# ESP32_WI-FI_Module.net
KiCad netlist of a schematic drawn in Altium Designer
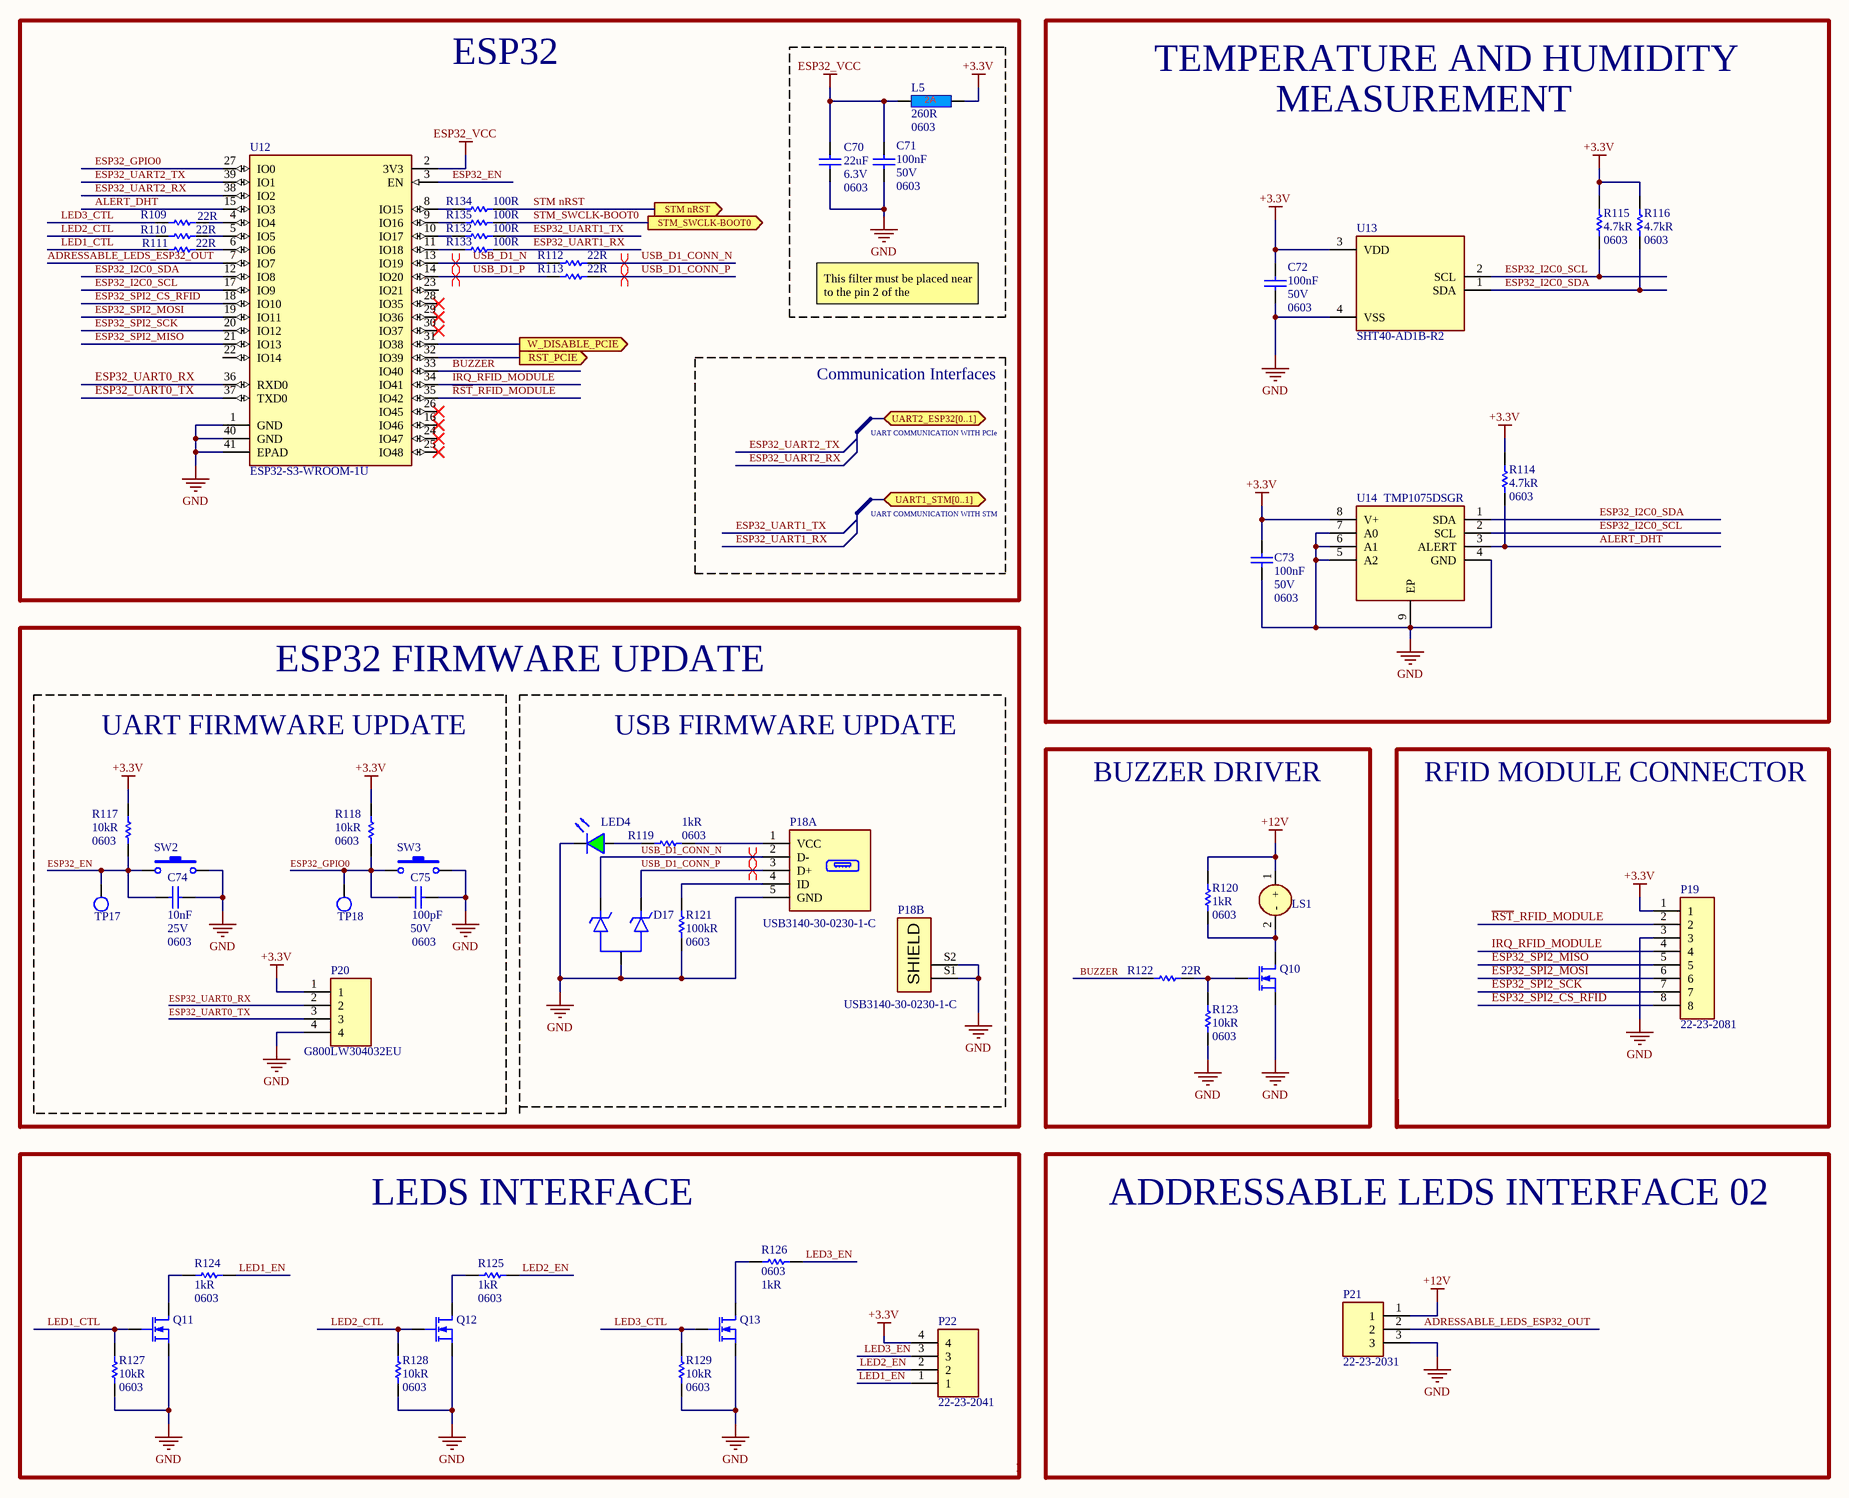
[diagram p0: ESP32 WI-FI Module.SchDoc]

(export (version "E")
  (design (tool "Eeschema 10.0.6"))
  (components
    (comp (ref "C70")
      (value "C_0603_22uF_6.3V_20%")
      (footprint "C0603")
      (description "CAP CER 22UF 6.3V X5R 0603")
      (fields
        (field (name "MANUFACTURER") "Murata")
        (field (name "MANUFACTURER PART NUMBER") "GRM188R60J226MEA0J")
        (field (name "CASE/PACKAGE") "0603")
        (field (name "VOLTAGE RATING (DC)") "6.3V")
        (field (name "CAPACITANCE") "22uF")
      )
      (libsource (lib "Power2Go - REV05") (part "C_0603_22uF_6.3V_20%"))
    )
    (comp (ref "C71")
      (value "100nF")
      (footprint "C0603")
      (description "Cap Ceramic 50V 20% +Tol 20% -Tol X7R 15% TC 0.1uF SMD 0603")
      (fields
        (field (name "MANUFACTURER") "Yageo")
        (field (name "MANUFACTURER PART NUMBER") "CC0603MRX7R9BB104")
        (field (name "CASE/PACKAGE") "0603")
        (field (name "VOLTAGE RATING") "50V")
      )
      (libsource (lib "Power2Go - REV05") (part "C_0603_0.1uF_50V_20%"))
    )
    (comp (ref "C72")
      (value "100nF")
      (footprint "C0603")
      (description "Cap Ceramic 50V 20% +Tol 20% -Tol X7R 15% TC 0.1uF SMD 0603")
      (fields
        (field (name "MANUFACTURER") "Yageo")
        (field (name "MANUFACTURER PART NUMBER") "CC0603MRX7R9BB104")
        (field (name "CASE/PACKAGE") "0603")
        (field (name "VOLTAGE RATING") "50V")
      )
      (libsource (lib "Power2Go - REV05") (part "C_0603_0.1uF_50V_20%"))
    )
    (comp (ref "C73")
      (value "100nF")
      (footprint "C0603")
      (description "Cap Ceramic 50V 20% +Tol 20% -Tol X7R 15% TC 0.1uF SMD 0603")
      (fields
        (field (name "MANUFACTURER") "Yageo")
        (field (name "MANUFACTURER PART NUMBER") "CC0603MRX7R9BB104")
        (field (name "CASE/PACKAGE") "0603")
        (field (name "VOLTAGE RATING") "50V")
      )
      (libsource (lib "Power2Go - REV05") (part "C_0603_0.1uF_50V_20%"))
    )
    (comp (ref "C74")
      (value "C_0603_0.01uF_25V_10%")
      (footprint "C0603")
      (description "Surface Mount Ceramic Multilayer Capacitor 0.01uF 10% X7R 25V 0603 Paper T/R")
      (fields
        (field (name "MANUFACTURER") "Yageo")
        (field (name "MANUFACTURER PART NUMBER") "CC0603KRX7R8BB103")
        (field (name "VOLTAGE RATING") "25V")
        (field (name "CAPACITANCE") "10nF")
        (field (name "CASE CODE (IMPERIAL)") "0603")
      )
      (libsource (lib "Power2Go - REV05") (part "C_0603_0.01uF_25V_10%"))
    )
    (comp (ref "C75")
      (value "100pF")
      (footprint "C0603")
      (description "Ceramic capacitor SMD-0603 100pF /50V NP0# J +-5%, Samsung, RoHS")
      (fields
        (field (name "MANUFACTURER") "Samsung")
        (field (name "MANUFACTURER PART NUMBER") "CL10C101JB8NNNC")
        (field (name "VOLTAGE") "50V")
        (field (name "CASE/PACKAGE") "0603")
      )
      (libsource (lib "Power2Go - REV05") (part "C_0603_100pF_50V_5%"))
    )
    (comp (ref "D17")
      (value "RCLAMP0502BATCT")
      (footprint "SC-75-3")
      (description "ESD Suppressor Diode TVS Uni-Dir/Bi-Dir 5V 3-Pin SOT-523 T/R / TVS DIODE 5VWM 25VC SC75")
      (fields (field (name "MANUFACTURER") "Semtech"))
      (libsource (lib "Power2Go - REV05") (part "D_TVS_RCLAMP0502BATCT"))
    )
    (comp (ref "L5")
      (value "BLM18EG221SN1D")
      (footprint "L0603")
      (description "Ferrite Chip, 1 Function(s), 1A, 2 Pin(s)")
      (fields
        (field (name "MANUFACTURER") "Murata")
        (field (name "CASE CODE") "0603")
        (field (name "OUTPUT IMPEDANCE") "260R")
      )
      (libsource (lib "Power2Go - REV05") (part "L_0603_25%_2A"))
    )
    (comp (ref "LED4")
      (value "LED 0603 SMD GREEN")
      (footprint "LED0603-GREEN")
      (description "Smd, Alingap, 0603, Thin, Grn, 571Nm, 35Mcd, Clr, T/R Rohs Compliant: Yes")
      (fields
        (field (name "MANUFACTURER") "Vishay Lite-On")
        (field (name "MANUFACTURER PART NUMBER") "LTST-C191KGKT")
      )
      (libsource (lib "Power2Go - REV05") (part "LED_0603_Green"))
    )
    (comp (ref "LS1")
      (value "PS1240P02BT")
      (footprint "BZ_12mm")
      (description "Piezo Buzzers & Audio Indicators Round 12.2mmx6.5mm 4kHz Vin=3V")
      (fields (field (name "MANUFACTURER") "TDK"))
      (libsource (lib "Power2Go - REV05") (part "LS_BUZZER_12mm"))
    )
    (comp (ref "P18")
      (value "USB3140-30-0230-1-C")
      (footprint "CONN-MICROUSB-VERT")
      (description "Conn Micro USB Type B RCP 2Power/3Signal POS Solder ST SMD 5 Terminal 2 Port T/R")
      (fields
        (field (name "MANUFACTURER") "Global Connector Technology")
        (field (name "MANUFACTURER PART NUMBER") "USB3140-30-0230-1-C")
      )
      (libsource (lib "Power2Go - REV05") (part "P_MicroUSB_TypeB"))
    )
    (comp (ref "P19")
      (value "22-23-2081")
      (footprint "HEADER_KK_2.54MM_8POS")
      (description "KK 254 Solid Header, Vertical, with Friction Lock, 8 Circuits, Tin (Sn) Plating")
      (fields (field (name "MANUFACTURER") "Molex") (field (name "MANUFACTURER PART NUMBER") "22-23-2081"))
      (libsource (lib "Power2Go - REV05") (part "P_Molex_HEADER_KK_8POS_2.54MM_PTH"))
    )
    (comp (ref "P20")
      (value "G800LW304032EU")
      (footprint "HEADER_2.54MM_4POS")
      (description "Board to Board Connector Straight Header Single Row 4 Position 2.54mm Pitch Through Hole Bag")
      (fields
        (field (name "MANUFACTURER") "Amphenol")
        (field (name "MANUFACTURER PART NUMBER") "G800LW304032EU")
      )
      (libsource (lib "Power2Go - REV05") (part "P_Header_2.54mm_4POS"))
    )
    (comp (ref "P21")
      (value "22-23-2031")
      (footprint "HEADER_2.54MM_3POS")
      (description "KK 254 Solid Header, Vertical, with Friction Lock, 3 Circuits, Tin (Sn) Plating, Bag")
      (fields (field (name "MANUFACTURER") "Molex") (field (name "MANUFACTURER PART NUMBER") "22-23-2031"))
      (libsource (lib "Power2Go - REV05") (part "P_Molex_HEADER_3POS_2.54MM_PTH"))
    )
    (comp (ref "P22")
      (value "22-23-2041")
      (footprint "HEADER_KK_2.54MM_4POS")
      (description "KK 254 Solid Header, Vertical, with Friction Lock, 4 Circuits, Tin (Sn) Plating")
      (fields (field (name "MANUFACTURER") "Molex"))
      (libsource (lib "Power2Go - REV05") (part "P_Molex_HEADER_KK_4POS_2.54MM_PTH"))
    )
    (comp (ref "Q10")
      (value "RSF015N06FRATL")
      (footprint "TUMT-3")
      (description "Transistor Mosfet N-ch 60V 1.5A 3-PIN Tumt T/r")
      (fields (field (name "MANUFACTURER") "Rohm"))
      (libsource (lib "Power2Go - REV05") (part "Q_RSF015N06FRATL_TUMT-3"))
    )
    (comp (ref "Q11")
      (value "RSF015N06FRATL")
      (footprint "TUMT-3")
      (description "Transistor Mosfet N-ch 60V 1.5A 3-PIN Tumt T/r")
      (fields (field (name "MANUFACTURER") "Rohm"))
      (libsource (lib "Power2Go - REV05") (part "Q_RSF015N06FRATL_TUMT-3"))
    )
    (comp (ref "Q12")
      (value "RSF015N06FRATL")
      (footprint "TUMT-3")
      (description "Transistor Mosfet N-ch 60V 1.5A 3-PIN Tumt T/r")
      (fields (field (name "MANUFACTURER") "Rohm"))
      (libsource (lib "Power2Go - REV05") (part "Q_RSF015N06FRATL_TUMT-3"))
    )
    (comp (ref "Q13")
      (value "RSF015N06FRATL")
      (footprint "TUMT-3")
      (description "Transistor Mosfet N-ch 60V 1.5A 3-PIN Tumt T/r")
      (fields (field (name "MANUFACTURER") "Rohm"))
      (libsource (lib "Power2Go - REV05") (part "Q_RSF015N06FRATL_TUMT-3"))
    )
    (comp (ref "R109")
      (value "CRCW060322R0FKEAC")
      (footprint "R0603")
      (description "Thick Film Resistors - SMD 1/10Watt 22ohms 1% Commercial Use")
      (fields
        (field (name "MANUFACTURER") "Vishay")
        (field (name "TOLERANCE") "1%")
        (field (name "RESISTANCE") "22R")
      )
      (libsource (lib "Power2Go - REV05") (part "R_0603_22R_1%_1/10W"))
    )
    (comp (ref "R110")
      (value "CRCW060322R0FKEAC")
      (footprint "R0603")
      (description "Thick Film Resistors - SMD 1/10Watt 22ohms 1% Commercial Use")
      (fields
        (field (name "MANUFACTURER") "Vishay")
        (field (name "TOLERANCE") "1%")
        (field (name "RESISTANCE") "22R")
      )
      (libsource (lib "Power2Go - REV05") (part "R_0603_22R_1%_1/10W"))
    )
    (comp (ref "R111")
      (value "CRCW060322R0FKEAC")
      (footprint "R0603")
      (description "Thick Film Resistors - SMD 1/10Watt 22ohms 1% Commercial Use")
      (fields
        (field (name "MANUFACTURER") "Vishay")
        (field (name "TOLERANCE") "1%")
        (field (name "RESISTANCE") "22R")
      )
      (libsource (lib "Power2Go - REV05") (part "R_0603_22R_1%_1/10W"))
    )
    (comp (ref "R112")
      (value "CRCW060322R0FKEAC")
      (footprint "R0603")
      (description "Thick Film Resistors - SMD 1/10Watt 22ohms 1% Commercial Use")
      (fields
        (field (name "MANUFACTURER") "Vishay")
        (field (name "TOLERANCE") "1%")
        (field (name "RESISTANCE") "22R")
      )
      (libsource (lib "Power2Go - REV05") (part "R_0603_22R_1%_1/10W"))
    )
    (comp (ref "R113")
      (value "CRCW060322R0FKEAC")
      (footprint "R0603")
      (description "Thick Film Resistors - SMD 1/10Watt 22ohms 1% Commercial Use")
      (fields
        (field (name "MANUFACTURER") "Vishay")
        (field (name "TOLERANCE") "1%")
        (field (name "RESISTANCE") "22R")
      )
      (libsource (lib "Power2Go - REV05") (part "R_0603_22R_1%_1/10W"))
    )
    (comp (ref "R114")
      (value "R_0603_4.7k_1%_1/10W")
      (footprint "R0603")
      (description "Res Thick Film 0603 4.7K Ohm 1% 0.1W(1/10W) ±100ppm/C Pad SMD T/R")
      (fields
        (field (name "TOLERANCE") "1%")
        (field (name "MANUFACTURER") "Mitsubishi Kamaya")
        (field (name "CASE CODE (IMPERIAL)") "0603")
        (field (name "RESISTANCE") "4.7kR")
      )
      (libsource (lib "Power2Go - REV05") (part "R_0603_4.7k_1%_1/10W"))
    )
    (comp (ref "R115")
      (value "R_0603_4.7k_1%_1/10W")
      (footprint "R0603")
      (description "Res Thick Film 0603 4.7K Ohm 1% 0.1W(1/10W) ±100ppm/C Pad SMD T/R")
      (fields
        (field (name "TOLERANCE") "1%")
        (field (name "MANUFACTURER") "Mitsubishi Kamaya")
        (field (name "CASE CODE (IMPERIAL)") "0603")
        (field (name "RESISTANCE") "4.7kR")
      )
      (libsource (lib "Power2Go - REV05") (part "R_0603_4.7k_1%_1/10W"))
    )
    (comp (ref "R116")
      (value "R_0603_4.7k_1%_1/10W")
      (footprint "R0603")
      (description "Res Thick Film 0603 4.7K Ohm 1% 0.1W(1/10W) ±100ppm/C Pad SMD T/R")
      (fields
        (field (name "TOLERANCE") "1%")
        (field (name "MANUFACTURER") "Mitsubishi Kamaya")
        (field (name "CASE CODE (IMPERIAL)") "0603")
        (field (name "RESISTANCE") "4.7kR")
      )
      (libsource (lib "Power2Go - REV05") (part "R_0603_4.7k_1%_1/10W"))
    )
    (comp (ref "R117")
      (value "10kR")
      (footprint "R0603")
      (fields
        (field (name "MANUFACTURER") "Vishay")
        (field (name "MANUFACTURER PART NUMBER") "CRCW060310K0JNEBC")
        (field (name "TOLERANCE") "5%")
        (field (name "CASE/PACKAGE") "0603")
      )
      (libsource (lib "Power2Go - REV05") (part "R_0603_10kR_5%_1/10W"))
    )
    (comp (ref "R118")
      (value "10kR")
      (footprint "R0603")
      (fields
        (field (name "MANUFACTURER") "Vishay")
        (field (name "MANUFACTURER PART NUMBER") "CRCW060310K0JNEBC")
        (field (name "TOLERANCE") "5%")
        (field (name "CASE/PACKAGE") "0603")
      )
      (libsource (lib "Power2Go - REV05") (part "R_0603_10kR_5%_1/10W"))
    )
    (comp (ref "R119")
      (value "R_0603_1kR_1%_1/10W")
      (footprint "R0603")
      (description "Res Thick Film 0603 1K Ohm 1% 1/10W ±100ppm/°C Molded SMD Paper T/R")
      (fields
        (field (name "MANUFACTURER") "Vishay")
        (field (name "MANUFACTURER PART NUMBER") "CRCW06031K00FKEAC")
        (field (name "SIZE CODE") "0603")
        (field (name "RESISTANCE") "1kR")
      )
      (libsource (lib "Power2Go - REV05") (part "R_0603_1kR_1%_1/10W"))
    )
    (comp (ref "R120")
      (value "R_0603_1kR_1%_1/10W")
      (footprint "R0603")
      (description "Res Thick Film 0603 1K Ohm 1% 1/10W ±100ppm/°C Molded SMD Paper T/R")
      (fields
        (field (name "MANUFACTURER") "Vishay")
        (field (name "MANUFACTURER PART NUMBER") "CRCW06031K00FKEAC")
        (field (name "SIZE CODE") "0603")
        (field (name "RESISTANCE") "1kR")
      )
      (libsource (lib "Power2Go - REV05") (part "R_0603_1kR_1%_1/10W"))
    )
    (comp (ref "R121")
      (value "RC0603FR-07100KL")
      (footprint "R0603")
      (description "Thick Film Resistors - SMD 100K OHM 1%")
      (fields
        (field (name "MANUFACTURER") "Yageo")
        (field (name "TOLERANCE") "1%")
        (field (name "CASE/PACKAGE") "0603")
        (field (name "RESISTANCE") "100kR")
      )
      (libsource (lib "Power2Go - REV05") (part "R_0603_100k_1%_1/10W"))
    )
    (comp (ref "R122")
      (value "CRCW060322R0FKEAC")
      (footprint "R0603")
      (description "Thick Film Resistors - SMD 1/10Watt 22ohms 1% Commercial Use")
      (fields
        (field (name "MANUFACTURER") "Vishay")
        (field (name "TOLERANCE") "1%")
        (field (name "RESISTANCE") "22R")
      )
      (libsource (lib "Power2Go - REV05") (part "R_0603_22R_1%_1/10W"))
    )
    (comp (ref "R123")
      (value "10kR")
      (footprint "R0603")
      (fields
        (field (name "MANUFACTURER") "Vishay")
        (field (name "MANUFACTURER PART NUMBER") "CRCW060310K0JNEBC")
        (field (name "TOLERANCE") "5%")
        (field (name "CASE/PACKAGE") "0603")
      )
      (libsource (lib "Power2Go - REV05") (part "R_0603_10kR_5%_1/10W"))
    )
    (comp (ref "R124")
      (value "R_0603_1kR_1%_1/10W")
      (footprint "R0603")
      (description "Res Thick Film 0603 1K Ohm 1% 1/10W ±100ppm/°C Molded SMD Paper T/R")
      (fields
        (field (name "MANUFACTURER") "Vishay")
        (field (name "MANUFACTURER PART NUMBER") "CRCW06031K00FKEAC")
        (field (name "SIZE CODE") "0603")
        (field (name "RESISTANCE") "1kR")
      )
      (libsource (lib "Power2Go - REV05") (part "R_0603_1kR_1%_1/10W"))
    )
    (comp (ref "R125")
      (value "R_0603_1kR_1%_1/10W")
      (footprint "R0603")
      (description "Res Thick Film 0603 1K Ohm 1% 1/10W ±100ppm/°C Molded SMD Paper T/R")
      (fields
        (field (name "MANUFACTURER") "Vishay")
        (field (name "MANUFACTURER PART NUMBER") "CRCW06031K00FKEAC")
        (field (name "SIZE CODE") "0603")
        (field (name "RESISTANCE") "1kR")
      )
      (libsource (lib "Power2Go - REV05") (part "R_0603_1kR_1%_1/10W"))
    )
    (comp (ref "R126")
      (value "R_0603_1kR_1%_1/10W")
      (footprint "R0603")
      (description "Res Thick Film 0603 1K Ohm 1% 1/10W ±100ppm/°C Molded SMD Paper T/R")
      (fields
        (field (name "MANUFACTURER") "Vishay")
        (field (name "MANUFACTURER PART NUMBER") "CRCW06031K00FKEAC")
        (field (name "SIZE CODE") "0603")
        (field (name "RESISTANCE") "1kR")
      )
      (libsource (lib "Power2Go - REV05") (part "R_0603_1kR_1%_1/10W"))
    )
    (comp (ref "R127")
      (value "10kR")
      (footprint "R0603")
      (fields
        (field (name "MANUFACTURER") "Vishay")
        (field (name "MANUFACTURER PART NUMBER") "CRCW060310K0JNEBC")
        (field (name "TOLERANCE") "5%")
        (field (name "CASE/PACKAGE") "0603")
      )
      (libsource (lib "Power2Go - REV05") (part "R_0603_10kR_5%_1/10W"))
    )
    (comp (ref "R128")
      (value "10kR")
      (footprint "R0603")
      (fields
        (field (name "MANUFACTURER") "Vishay")
        (field (name "MANUFACTURER PART NUMBER") "CRCW060310K0JNEBC")
        (field (name "TOLERANCE") "5%")
        (field (name "CASE/PACKAGE") "0603")
      )
      (libsource (lib "Power2Go - REV05") (part "R_0603_10kR_5%_1/10W"))
    )
    (comp (ref "R129")
      (value "10kR")
      (footprint "R0603")
      (fields
        (field (name "MANUFACTURER") "Vishay")
        (field (name "MANUFACTURER PART NUMBER") "CRCW060310K0JNEBC")
        (field (name "TOLERANCE") "5%")
        (field (name "CASE/PACKAGE") "0603")
      )
      (libsource (lib "Power2Go - REV05") (part "R_0603_10kR_5%_1/10W"))
    )
    (comp (ref "R132")
      (value "100R")
      (footprint "R0603")
      (description "Res Thin Film 0603 100 Ohm 1% 1/10W ±25ppm/°C Molded SMD Paper Tape on Plastic Reel")
      (fields
        (field (name "MANUFACTURER") "Bourns")
        (field (name "MANUFACTURER PART NUMBER") "CRT0603-FY-1000ELF")
      )
      (libsource (lib "Power2Go - REV05") (part "R_0603_100R_1%_1/10W_25PPM"))
    )
    (comp (ref "R133")
      (value "100R")
      (footprint "R0603")
      (description "Res Thin Film 0603 100 Ohm 1% 1/10W ±25ppm/°C Molded SMD Paper Tape on Plastic Reel")
      (fields
        (field (name "MANUFACTURER") "Bourns")
        (field (name "MANUFACTURER PART NUMBER") "CRT0603-FY-1000ELF")
      )
      (libsource (lib "Power2Go - REV05") (part "R_0603_100R_1%_1/10W_25PPM"))
    )
    (comp (ref "R134")
      (value "100R")
      (footprint "R0603")
      (description "Res Thin Film 0603 100 Ohm 1% 1/10W ±25ppm/°C Molded SMD Paper Tape on Plastic Reel")
      (fields
        (field (name "MANUFACTURER") "Bourns")
        (field (name "MANUFACTURER PART NUMBER") "CRT0603-FY-1000ELF")
      )
      (libsource (lib "Power2Go - REV05") (part "R_0603_100R_1%_1/10W_25PPM"))
    )
    (comp (ref "R135")
      (value "100R")
      (footprint "R0603")
      (description "Res Thin Film 0603 100 Ohm 1% 1/10W ±25ppm/°C Molded SMD Paper Tape on Plastic Reel")
      (fields
        (field (name "MANUFACTURER") "Bourns")
        (field (name "MANUFACTURER PART NUMBER") "CRT0603-FY-1000ELF")
      )
      (libsource (lib "Power2Go - REV05") (part "R_0603_100R_1%_1/10W_25PPM"))
    )
    (comp (ref "SW2")
      (value "PTS810SJM250SMTRLFS")
      (footprint "PUSH BUTTON 4.2mm x 3.2 mm")
      (description "SWITCHTACTILESPST-NO0.05A16V")
      (fields (field (name "MANUFACTURER") "ITT C&K"))
      (libsource (lib "Power2Go - REV05") (part "B_PushButton_PTS810SJM250SMTRLFS"))
    )
    (comp (ref "SW3")
      (value "PTS810SJM250SMTRLFS")
      (footprint "PUSH BUTTON 4.2mm x 3.2 mm")
      (description "SWITCHTACTILESPST-NO0.05A16V")
      (fields (field (name "MANUFACTURER") "ITT C&K"))
      (libsource (lib "Power2Go - REV05") (part "B_PushButton_PTS810SJM250SMTRLFS"))
    )
    (comp (ref "TP17")
      (value "TP_SMT_CIRCLE")
      (footprint "Test Point 1.5 mm")
      (libsource (lib "Power2Go - REV05") (part "TP_SMT_CIRCLE"))
    )
    (comp (ref "TP18")
      (value "TP_SMT_CIRCLE")
      (footprint "Test Point 1.5 mm")
      (libsource (lib "Power2Go - REV05") (part "TP_SMT_CIRCLE"))
    )
    (comp (ref "U12")
      (value "U_ESP32-S3-WROOM-1U")
      (footprint "ESP32-S3-WROOM-1U")
      (fields
        (field (name "MF") "Espressif Systems")
        (field (name "MANUFACTURER PART NUMBER") "ESP32-S3-WROOM-1U-N16R8")
        (field (name "MP") "ESP32-S3-WROOM-1U")
      )
      (libsource (lib "Power2Go - REV05") (part "U_ESP32-S3-WROOM-1U"))
    )
    (comp (ref "U13")
      (value "SHT40-AD1B-R2")
      (footprint "DFN-4")
      (description "Humidity/Temperature Sensor Digital Serial (I2C) 4-Pin DFN EP T/R")
      (fields
        (field (name "MANUFACTURER") "Sensirion")
        (field (name "MANUFACTURER PART NUMBER") "SHT40-AD1B-R2")
      )
      (libsource (lib "Power2Go - REV05") (part "U_SHT40-AD1B-R2_DFN-4"))
    )
    (comp (ref "U14")
      (value "TMP1075DSGR")
      (footprint "WSON8")
      (fields
        (field (name "MANUFACTURER") "Texas Instruments")
        (field (name "MANUFACTURER PART NUMBER") "TMP1075DSGR")
      )
      (libsource (lib "Power2Go - REV05") (part "U_TMP1075DSGR_WSON-8"))
    )
  )
  (nets
    (net (code "5") (name "+3.3V") (class "Default")
      (node (ref "C72") (pin "1") (pinfunction "1_1") (pintype "passive"))
      (node (ref "C73") (pin "1") (pinfunction "1_1") (pintype "passive"))
      (node (ref "L5") (pin "2") (pinfunction "2_2") (pintype "passive"))
      (node (ref "P19") (pin "1") (pinfunction "1_1") (pintype "passive"))
      (node (ref "P20") (pin "1") (pinfunction "1_1") (pintype "passive"))
      (node (ref "P22") (pin "4") (pinfunction "4_4") (pintype "passive"))
      (node (ref "R114") (pin "2") (pinfunction "2_2") (pintype "passive"))
      (node (ref "R115") (pin "2") (pinfunction "2_2") (pintype "passive"))
      (node (ref "R116") (pin "2") (pinfunction "2_2") (pintype "passive"))
      (node (ref "R117") (pin "2") (pinfunction "2_2") (pintype "passive"))
      (node (ref "R118") (pin "2") (pinfunction "2_2") (pintype "passive"))
      (node (ref "U13") (pin "3") (pinfunction "VDD_3") (pintype "power_in"))
      (node (ref "U14") (pin "8") (pinfunction "V+_8") (pintype "passive"))
    )
    (net (code "6") (name "+12V") (class "Default")
      (node (ref "LS1") (pin "1") (pinfunction "+_1") (pintype "passive"))
      (node (ref "P21") (pin "1") (pinfunction "1_1") (pintype "passive"))
      (node (ref "R120") (pin "1") (pinfunction "1_1") (pintype "passive"))
    )
    (net (code "7") (name "/ADRESSABLE_LEDS_ESP32_OUT") (class "Default")
      (node (ref "P21") (pin "2") (pinfunction "2_2") (pintype "passive"))
      (node (ref "U12") (pin "7") (pinfunction "IO7_7") (pintype "bidirectional"))
    )
    (net (code "8") (name "/ALERT_DHT") (class "Default")
      (node (ref "R114") (pin "1") (pinfunction "1_1") (pintype "passive"))
      (node (ref "U12") (pin "15") (pinfunction "IO3_15") (pintype "bidirectional"))
      (node (ref "U14") (pin "3") (pinfunction "ALERT_3") (pintype "passive"))
    )
    (net (code "9") (name "/BUZZER") (class "Default")
      (node (ref "R122") (pin "2") (pinfunction "2_2") (pintype "passive"))
      (node (ref "U12") (pin "33") (pinfunction "IO40_33") (pintype "bidirectional"))
    )
    (net (code "10") (name "/ESP32_EN") (class "Default")
      (node (ref "C74") (pin "2") (pinfunction "2_2") (pintype "passive"))
      (node (ref "R117") (pin "1") (pinfunction "1_1") (pintype "passive"))
      (node (ref "SW2") (pin "1") (pinfunction "1_1") (pintype "passive"))
      (node (ref "TP17") (pin "1") (pinfunction "1_1") (pintype "passive"))
      (node (ref "U12") (pin "3") (pinfunction "EN_3") (pintype "input"))
    )
    (net (code "11") (name "/ESP32_GPIO0") (class "Default")
      (node (ref "C75") (pin "1") (pinfunction "1_1") (pintype "passive"))
      (node (ref "R118") (pin "1") (pinfunction "1_1") (pintype "passive"))
      (node (ref "SW3") (pin "1") (pinfunction "1_1") (pintype "passive"))
      (node (ref "TP18") (pin "1") (pinfunction "1_1") (pintype "passive"))
      (node (ref "U12") (pin "27") (pinfunction "IO0_27") (pintype "bidirectional"))
    )
    (net (code "12") (name "/ESP32_I2C0_SCL") (class "Default")
      (node (ref "R115") (pin "1") (pinfunction "1_1") (pintype "passive"))
      (node (ref "U12") (pin "17") (pinfunction "IO9_17") (pintype "bidirectional"))
      (node (ref "U13") (pin "2") (pinfunction "SCL_2") (pintype "passive"))
      (node (ref "U14") (pin "2") (pinfunction "SCL_2") (pintype "passive"))
    )
    (net (code "13") (name "/ESP32_I2C0_SDA") (class "Default")
      (node (ref "R116") (pin "1") (pinfunction "1_1") (pintype "passive"))
      (node (ref "U12") (pin "12") (pinfunction "IO8_12") (pintype "bidirectional"))
      (node (ref "U13") (pin "1") (pinfunction "SDA_1") (pintype "passive"))
      (node (ref "U14") (pin "1") (pinfunction "SDA_1") (pintype "passive"))
    )
    (net (code "14") (name "/ESP32_SPI2_CS_RFID") (class "Default")
      (node (ref "P19") (pin "8") (pinfunction "8_8") (pintype "passive"))
      (node (ref "U12") (pin "18") (pinfunction "IO10_18") (pintype "bidirectional"))
    )
    (net (code "15") (name "/ESP32_SPI2_MISO") (class "Default")
      (node (ref "P19") (pin "5") (pinfunction "5_5") (pintype "passive"))
      (node (ref "U12") (pin "21") (pinfunction "IO13_21") (pintype "bidirectional"))
    )
    (net (code "16") (name "/ESP32_SPI2_MOSI") (class "Default")
      (node (ref "P19") (pin "6") (pinfunction "6_6") (pintype "passive"))
      (node (ref "U12") (pin "19") (pinfunction "IO11_19") (pintype "bidirectional"))
    )
    (net (code "17") (name "/ESP32_SPI2_SCK") (class "Default")
      (node (ref "P19") (pin "7") (pinfunction "7_7") (pintype "passive"))
      (node (ref "U12") (pin "20") (pinfunction "IO12_20") (pintype "bidirectional"))
    )
    (net (code "18") (name "/ESP32_UART0_RX") (class "Default")
      (node (ref "P20") (pin "2") (pinfunction "2_2") (pintype "passive"))
      (node (ref "U12") (pin "36") (pinfunction "RXD0_36") (pintype "bidirectional"))
    )
    (net (code "19") (name "/ESP32_UART0_TX") (class "Default")
      (node (ref "P20") (pin "3") (pinfunction "3_3") (pintype "passive"))
      (node (ref "U12") (pin "37") (pinfunction "TXD0_37") (pintype "bidirectional"))
    )
    (net (code "20") (name "/ESP32_UART1_RX") (class "Default")
      (node (ref "R133") (pin "2") (pinfunction "2_2") (pintype "passive"))
    )
    (net (code "21") (name "/ESP32_UART1_TX") (class "Default")
      (node (ref "R132") (pin "2") (pinfunction "2_2") (pintype "passive"))
    )
    (net (code "22") (name "/ESP32_UART2_RX") (class "Default")
      (node (ref "U12") (pin "38") (pinfunction "IO2_38") (pintype "bidirectional"))
    )
    (net (code "23") (name "/ESP32_UART2_TX") (class "Default")
      (node (ref "U12") (pin "39") (pinfunction "IO1_39") (pintype "bidirectional"))
    )
    (net (code "24") (name "/IRQ_RFID_MODULE") (class "Default")
      (node (ref "P19") (pin "4") (pinfunction "4_4") (pintype "passive"))
      (node (ref "U12") (pin "34") (pinfunction "IO41_34") (pintype "bidirectional"))
    )
    (net (code "25") (name "/LED1_CTL") (class "Default")
      (node (ref "Q11") (pin "1") (pinfunction "G_1") (pintype "passive"))
      (node (ref "R111") (pin "2") (pinfunction "2_2") (pintype "passive"))
      (node (ref "R127") (pin "2") (pinfunction "2_2") (pintype "passive"))
    )
    (net (code "26") (name "/LED1_EN") (class "Default")
      (node (ref "P22") (pin "1") (pinfunction "1_1") (pintype "passive"))
      (node (ref "R124") (pin "2") (pinfunction "2_2") (pintype "passive"))
    )
    (net (code "27") (name "/LED2_CTL") (class "Default")
      (node (ref "Q12") (pin "1") (pinfunction "G_1") (pintype "passive"))
      (node (ref "R110") (pin "2") (pinfunction "2_2") (pintype "passive"))
      (node (ref "R128") (pin "2") (pinfunction "2_2") (pintype "passive"))
    )
    (net (code "28") (name "/LED2_EN") (class "Default")
      (node (ref "P22") (pin "2") (pinfunction "2_2") (pintype "passive"))
      (node (ref "R125") (pin "2") (pinfunction "2_2") (pintype "passive"))
    )
    (net (code "29") (name "/LED3_CTL") (class "Default")
      (node (ref "Q13") (pin "1") (pinfunction "G_1") (pintype "passive"))
      (node (ref "R109") (pin "2") (pinfunction "2_2") (pintype "passive"))
      (node (ref "R129") (pin "2") (pinfunction "2_2") (pintype "passive"))
    )
    (net (code "30") (name "/LED3_EN") (class "Default")
      (node (ref "P22") (pin "3") (pinfunction "3_3") (pintype "passive"))
      (node (ref "R126") (pin "2") (pinfunction "2_2") (pintype "passive"))
    )
    (net (code "31") (name "/RST_PCIE") (class "Default")
      (node (ref "U12") (pin "32") (pinfunction "IO39_32") (pintype "bidirectional"))
    )
    (net (code "32") (name "/STM nRST") (class "Default")
      (node (ref "R134") (pin "2") (pinfunction "2_2") (pintype "passive"))
    )
    (net (code "33") (name "/STM_SWCLK-BOOT0") (class "Default")
      (node (ref "R135") (pin "2") (pinfunction "2_2") (pintype "passive"))
    )
    (net (code "36") (name "/USB_D1_CONN_N") (class "Default")
      (node (ref "D17") (pin "1") (pinfunction "K_1") (pintype "passive"))
      (node (ref "P18") (pin "2") (pinfunction "D-_2") (pintype "passive"))
      (node (ref "R112") (pin "2") (pinfunction "2_2") (pintype "passive"))
    )
    (net (code "37") (name "/USB_D1_CONN_P") (class "Default")
      (node (ref "D17") (pin "2") (pinfunction "K_2") (pintype "passive"))
      (node (ref "P18") (pin "3") (pinfunction "D+_3") (pintype "passive"))
      (node (ref "R113") (pin "2") (pinfunction "2_2") (pintype "passive"))
    )
    (net (code "38") (name "/USB_D1_N") (class "Default")
      (node (ref "R112") (pin "1") (pinfunction "1_1") (pintype "passive"))
      (node (ref "U12") (pin "13") (pinfunction "IO19_13") (pintype "bidirectional"))
    )
    (net (code "39") (name "/USB_D1_P") (class "Default")
      (node (ref "R113") (pin "1") (pinfunction "1_1") (pintype "passive"))
      (node (ref "U12") (pin "14") (pinfunction "IO20_14") (pintype "bidirectional"))
    )
    (net (code "40") (name "/W_DISABLE_PCIE") (class "Default")
      (node (ref "U12") (pin "31") (pinfunction "IO38_31") (pintype "bidirectional"))
    )
    (net (code "41") (name "/~{RST}_RFID_MODULE") (class "Default")
      (node (ref "P19") (pin "2") (pinfunction "2_2") (pintype "passive"))
      (node (ref "U12") (pin "35") (pinfunction "IO42_35") (pintype "bidirectional"))
    )
    (net (code "42") (name "ESP32_VCC") (class "Default")
      (node (ref "C70") (pin "2") (pinfunction "2_2") (pintype "passive"))
      (node (ref "C71") (pin "1") (pinfunction "1_1") (pintype "passive"))
      (node (ref "L5") (pin "1") (pinfunction "1_1") (pintype "passive"))
      (node (ref "U12") (pin "2") (pinfunction "3V3_2") (pintype "power_in"))
    )
    (net (code "43") (name "GND") (class "Default")
      (node (ref "C70") (pin "1") (pinfunction "1_1") (pintype "passive"))
      (node (ref "C71") (pin "2") (pinfunction "2_2") (pintype "passive"))
      (node (ref "C72") (pin "2") (pinfunction "2_2") (pintype "passive"))
      (node (ref "C73") (pin "2") (pinfunction "2_2") (pintype "passive"))
      (node (ref "C74") (pin "1") (pinfunction "1_1") (pintype "passive"))
      (node (ref "C75") (pin "2") (pinfunction "2_2") (pintype "passive"))
      (node (ref "D17") (pin "3") (pinfunction "A_3") (pintype "passive"))
      (node (ref "LED4") (pin "2") (pinfunction "K_2") (pintype "passive"))
      (node (ref "P18") (pin "5") (pinfunction "GND_5") (pintype "power_in"))
      (node (ref "P18") (pin "S1") (pinfunction "SHIELD_S1") (pintype "passive"))
      (node (ref "P18") (pin "S2") (pinfunction "SHIELD_S2") (pintype "passive"))
      (node (ref "P19") (pin "3") (pinfunction "3_3") (pintype "passive"))
      (node (ref "P20") (pin "4") (pinfunction "4_4") (pintype "passive"))
      (node (ref "P21") (pin "3") (pinfunction "3_3") (pintype "passive"))
      (node (ref "Q10") (pin "2") (pinfunction "S_2") (pintype "passive"))
      (node (ref "Q11") (pin "2") (pinfunction "S_2") (pintype "passive"))
      (node (ref "Q12") (pin "2") (pinfunction "S_2") (pintype "passive"))
      (node (ref "Q13") (pin "2") (pinfunction "S_2") (pintype "passive"))
      (node (ref "R121") (pin "1") (pinfunction "1_1") (pintype "passive"))
      (node (ref "R123") (pin "1") (pinfunction "1_1") (pintype "passive"))
      (node (ref "R127") (pin "1") (pinfunction "1_1") (pintype "passive"))
      (node (ref "R128") (pin "1") (pinfunction "1_1") (pintype "passive"))
      (node (ref "R129") (pin "1") (pinfunction "1_1") (pintype "passive"))
      (node (ref "SW2") (pin "3") (pinfunction "3_3") (pintype "passive"))
      (node (ref "SW3") (pin "3") (pinfunction "3_3") (pintype "passive"))
      (node (ref "U12") (pin "1") (pinfunction "GND_1") (pintype "power_in"))
      (node (ref "U12") (pin "40") (pinfunction "GND_40") (pintype "power_in"))
      (node (ref "U12") (pin "41") (pinfunction "EPAD_41") (pintype "power_in"))
      (node (ref "U13") (pin "4") (pinfunction "VSS_4") (pintype "power_in"))
      (node (ref "U14") (pin "4") (pinfunction "GND_4") (pintype "passive"))
      (node (ref "U14") (pin "5") (pinfunction "A2_5") (pintype "passive"))
      (node (ref "U14") (pin "6") (pinfunction "A1_6") (pintype "passive"))
      (node (ref "U14") (pin "7") (pinfunction "A0_7") (pintype "passive"))
      (node (ref "U14") (pin "9") (pinfunction "EP_9") (pintype "passive"))
    )
    (net (code "44") (name "Net-(LED4-A)") (class "Default")
      (node (ref "LED4") (pin "1") (pinfunction "A_1") (pintype "passive"))
      (node (ref "R119") (pin "2") (pinfunction "2_2") (pintype "passive"))
    )
    (net (code "45") (name "Net-(LS1--)") (class "Default")
      (node (ref "LS1") (pin "2") (pinfunction "-_2") (pintype "passive"))
      (node (ref "Q10") (pin "3") (pinfunction "D_3") (pintype "passive"))
      (node (ref "R120") (pin "2") (pinfunction "2_2") (pintype "passive"))
    )
    (net (code "46") (name "Net-(P18A-ID)") (class "Default")
      (node (ref "P18") (pin "4") (pinfunction "ID_4") (pintype "passive"))
      (node (ref "R121") (pin "2") (pinfunction "2_2") (pintype "passive"))
    )
    (net (code "47") (name "Net-(P18A-VCC)") (class "Default")
      (node (ref "P18") (pin "1") (pinfunction "VCC_1") (pintype "power_in"))
      (node (ref "R119") (pin "1") (pinfunction "1_1") (pintype "passive"))
    )
    (net (code "48") (name "Net-(Q10-G)") (class "Default")
      (node (ref "Q10") (pin "1") (pinfunction "G_1") (pintype "passive"))
      (node (ref "R122") (pin "1") (pinfunction "1_1") (pintype "passive"))
      (node (ref "R123") (pin "2") (pinfunction "2_2") (pintype "passive"))
    )
    (net (code "49") (name "Net-(Q11-D)") (class "Default")
      (node (ref "Q11") (pin "3") (pinfunction "D_3") (pintype "passive"))
      (node (ref "R124") (pin "1") (pinfunction "1_1") (pintype "passive"))
    )
    (net (code "50") (name "Net-(Q12-D)") (class "Default")
      (node (ref "Q12") (pin "3") (pinfunction "D_3") (pintype "passive"))
      (node (ref "R125") (pin "1") (pinfunction "1_1") (pintype "passive"))
    )
    (net (code "51") (name "Net-(Q13-D)") (class "Default")
      (node (ref "Q13") (pin "3") (pinfunction "D_3") (pintype "passive"))
      (node (ref "R126") (pin "1") (pinfunction "1_1") (pintype "passive"))
    )
    (net (code "52") (name "Net-(U12-IO4)") (class "Default")
      (node (ref "R109") (pin "1") (pinfunction "1_1") (pintype "passive"))
      (node (ref "U12") (pin "4") (pinfunction "IO4_4") (pintype "bidirectional"))
    )
    (net (code "53") (name "Net-(U12-IO5)") (class "Default")
      (node (ref "R110") (pin "1") (pinfunction "1_1") (pintype "passive"))
      (node (ref "U12") (pin "5") (pinfunction "IO5_5") (pintype "bidirectional"))
    )
    (net (code "54") (name "Net-(U12-IO6)") (class "Default")
      (node (ref "R111") (pin "1") (pinfunction "1_1") (pintype "passive"))
      (node (ref "U12") (pin "6") (pinfunction "IO6_6") (pintype "bidirectional"))
    )
    (net (code "55") (name "Net-(U12-IO15)") (class "Default")
      (node (ref "R134") (pin "1") (pinfunction "1_1") (pintype "passive"))
      (node (ref "U12") (pin "8") (pinfunction "IO15_8") (pintype "bidirectional"))
    )
    (net (code "56") (name "Net-(U12-IO16)") (class "Default")
      (node (ref "R135") (pin "1") (pinfunction "1_1") (pintype "passive"))
      (node (ref "U12") (pin "9") (pinfunction "IO16_9") (pintype "bidirectional"))
    )
    (net (code "57") (name "Net-(U12-IO17)") (class "Default")
      (node (ref "R132") (pin "1") (pinfunction "1_1") (pintype "passive"))
      (node (ref "U12") (pin "10") (pinfunction "IO17_10") (pintype "bidirectional"))
    )
    (net (code "58") (name "Net-(U12-IO18)") (class "Default")
      (node (ref "R133") (pin "1") (pinfunction "1_1") (pintype "passive"))
      (node (ref "U12") (pin "11") (pinfunction "IO18_11") (pintype "bidirectional"))
    )
    (net (code "59") (name "unconnected-(U12-IO14-Pad22)") (class "Default")
      (node (ref "U12") (pin "22") (pinfunction "IO14_22") (pintype "bidirectional"))
    )
    (net (code "60") (name "unconnected-(U12-IO21-Pad23)") (class "Default")
      (node (ref "U12") (pin "23") (pinfunction "IO21_23") (pintype "bidirectional"))
    )
    (net (code "61") (name "unconnected-(U12-IO35-Pad28)") (class "Default")
      (node (ref "U12") (pin "28") (pinfunction "IO35_28") (pintype "bidirectional+no_connect"))
    )
    (net (code "62") (name "unconnected-(U12-IO36-Pad29)") (class "Default")
      (node (ref "U12") (pin "29") (pinfunction "IO36_29") (pintype "bidirectional+no_connect"))
    )
    (net (code "63") (name "unconnected-(U12-IO37-Pad30)") (class "Default")
      (node (ref "U12") (pin "30") (pinfunction "IO37_30") (pintype "bidirectional+no_connect"))
    )
    (net (code "64") (name "unconnected-(U12-IO45-Pad26)") (class "Default")
      (node (ref "U12") (pin "26") (pinfunction "IO45_26") (pintype "bidirectional+no_connect"))
    )
    (net (code "65") (name "unconnected-(U12-IO46-Pad16)") (class "Default")
      (node (ref "U12") (pin "16") (pinfunction "IO46_16") (pintype "bidirectional+no_connect"))
    )
    (net (code "66") (name "unconnected-(U12-IO47-Pad24)") (class "Default")
      (node (ref "U12") (pin "24") (pinfunction "IO47_24") (pintype "bidirectional+no_connect"))
    )
    (net (code "67") (name "unconnected-(U12-IO48-Pad25)") (class "Default")
      (node (ref "U12") (pin "25") (pinfunction "IO48_25") (pintype "bidirectional+no_connect"))
    )
  )
)
